# USB-I2C.net
KiCad netlist of a schematic drawn in EAGLE
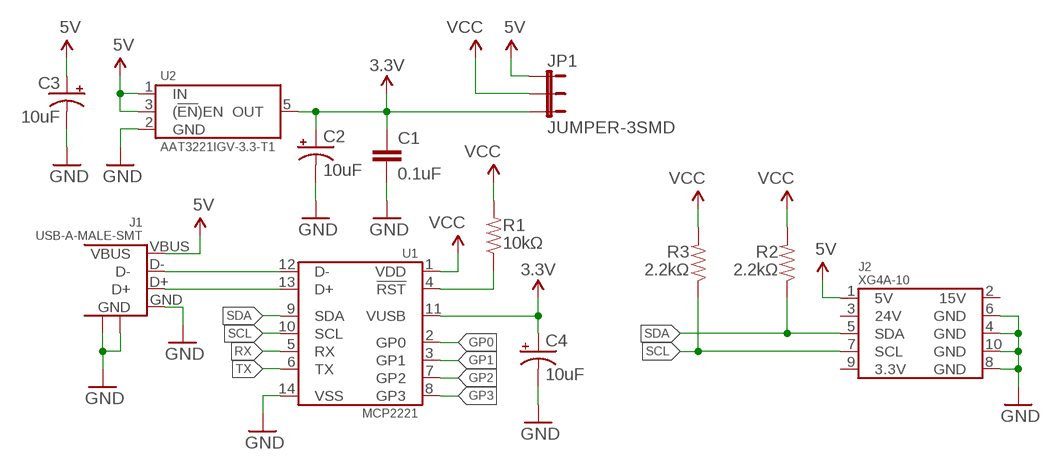
[diagram p0: schematic, sheet 1]

(export (version "E")
  (design (tool "Eeschema 10.0.6"))
  (components
    (comp (ref "C1")
      (value "0.1uF")
      (footprint "eagle-import:0805-CAP")
      (libsource (lib "eagle-import") (part "CAP-0805"))
    )
    (comp (ref "C2")
      (value "10uF")
      (footprint "eagle-import:0805-CAP_POL")
      (libsource (lib "eagle-import") (part "CAP_POL0805"))
    )
    (comp (ref "C3")
      (value "10uF")
      (footprint "eagle-import:0805-CAP_POL")
      (libsource (lib "eagle-import") (part "CAP_POL0805"))
    )
    (comp (ref "C4")
      (value "10uF")
      (footprint "eagle-import:0805-CAP_POL")
      (libsource (lib "eagle-import") (part "CAP_POL0805"))
    )
    (comp (ref "J1")
      (value "USB-A-MALE-SMT")
      (footprint "eagle-import:USB-A-MALE-SMT")
      (libsource (lib "eagle-import") (part "USB-A-MALE-SMT"))
    )
    (comp (ref "J2")
      (value "XG4A-10")
      (footprint "eagle-import:M05X2_SHROUD")
      (libsource (lib "eagle-import") (part "XG4A-10"))
    )
    (comp (ref "JP1")
      (value "JUMPER-3SMD")
      (footprint "eagle-import:SJ_3")
      (libsource (lib "eagle-import") (part "JUMPER-3SMD"))
    )
    (comp (ref "R1")
      (value "10kΩ")
      (footprint "eagle-import:0805-RES")
      (libsource (lib "eagle-import") (part "RESISTOR-0805"))
    )
    (comp (ref "R2")
      (value "2.2kΩ")
      (footprint "eagle-import:0805-RES")
      (libsource (lib "eagle-import") (part "RESISTOR-0805"))
    )
    (comp (ref "R3")
      (value "2.2kΩ")
      (footprint "eagle-import:0805-RES")
      (libsource (lib "eagle-import") (part "RESISTOR-0805"))
    )
    (comp (ref "U1")
      (value "MCP2221")
      (footprint "eagle-import:SOIC-14")
      (libsource (lib "eagle-import") (part "MCP2221"))
    )
    (comp (ref "U2")
      (value "AAT3221IGV-3.3-T1")
      (footprint "eagle-import:SOT23-5")
      (libsource (lib "eagle-import") (part "AAT3221IGV-3.3-T1"))
    )
  )
  (nets
    (net (code "1") (name "3.3V") (class "Default")
      (node (ref "C1") (pin "1") (pinfunction "1_1") (pintype "passive"))
      (node (ref "C2") (pin "A") (pinfunction "+_A") (pintype "passive"))
      (node (ref "C4") (pin "A") (pinfunction "+_A") (pintype "passive"))
      (node (ref "JP1") (pin "3") (pinfunction "3_3") (pintype "passive"))
      (node (ref "U1") (pin "11") (pinfunction "VUSB_11") (pintype "bidirectional"))
      (node (ref "U2") (pin "5") (pinfunction "OUT_5") (pintype "bidirectional"))
    )
    (net (code "2") (name "5V") (class "Default")
      (node (ref "C3") (pin "A") (pinfunction "+_A") (pintype "passive"))
      (node (ref "J1") (pin "VBUS") (pinfunction "VBUS_VBUS") (pintype "bidirectional"))
      (node (ref "J2") (pin "1") (pinfunction "5V_1") (pintype "bidirectional"))
      (node (ref "JP1") (pin "1") (pinfunction "1_1") (pintype "passive"))
      (node (ref "U2") (pin "1") (pinfunction "IN_1") (pintype "bidirectional"))
      (node (ref "U2") (pin "3") (pinfunction "(~{EN})EN_3") (pintype "bidirectional"))
    )
    (net (code "3") (name "GND") (class "Default")
      (node (ref "C1") (pin "2") (pinfunction "2_2") (pintype "passive"))
      (node (ref "C2") (pin "C") (pinfunction "-_C") (pintype "passive"))
      (node (ref "C3") (pin "C") (pinfunction "-_C") (pintype "passive"))
      (node (ref "C4") (pin "C") (pinfunction "-_C") (pintype "passive"))
      (node (ref "J1") (pin "GND") (pinfunction "GND_GND") (pintype "bidirectional"))
      (node (ref "J1") (pin "P$1") (pinfunction "P$1_P$1") (pintype "bidirectional"))
      (node (ref "J1") (pin "P$3") (pinfunction "P$2_P$3") (pintype "bidirectional"))
      (node (ref "J2") (pin "10") (pinfunction "GND_10") (pintype "bidirectional"))
      (node (ref "J2") (pin "4") (pinfunction "GND_4") (pintype "bidirectional"))
      (node (ref "J2") (pin "6") (pinfunction "GND_6") (pintype "bidirectional"))
      (node (ref "J2") (pin "8") (pinfunction "GND_8") (pintype "bidirectional"))
      (node (ref "U1") (pin "14") (pinfunction "VSS_14") (pintype "bidirectional"))
      (node (ref "U2") (pin "2") (pinfunction "GND_2") (pintype "bidirectional"))
    )
    (net (code "4") (name "GP0") (class "Default")
      (node (ref "U1") (pin "2") (pinfunction "GP0_2") (pintype "bidirectional"))
    )
    (net (code "5") (name "GP1") (class "Default")
      (node (ref "U1") (pin "3") (pinfunction "GP1_3") (pintype "bidirectional"))
    )
    (net (code "6") (name "GP2") (class "Default")
      (node (ref "U1") (pin "7") (pinfunction "GP2_7") (pintype "bidirectional"))
    )
    (net (code "7") (name "GP3") (class "Default")
      (node (ref "U1") (pin "8") (pinfunction "GP3_8") (pintype "bidirectional"))
    )
    (net (code "8") (name "Net-(U1-D+)") (class "Default")
      (node (ref "J1") (pin "D+") (pinfunction "D+_D+") (pintype "bidirectional"))
      (node (ref "U1") (pin "13") (pinfunction "D+_13") (pintype "bidirectional"))
    )
    (net (code "9") (name "Net-(U1-D-)") (class "Default")
      (node (ref "J1") (pin "D-") (pinfunction "D-_D-") (pintype "bidirectional"))
      (node (ref "U1") (pin "12") (pinfunction "D-_12") (pintype "bidirectional"))
    )
    (net (code "10") (name "Net-(U1-~{RST})") (class "Default")
      (node (ref "R1") (pin "1") (pinfunction "1_1") (pintype "passive"))
      (node (ref "U1") (pin "4") (pinfunction "~{RST}_4") (pintype "bidirectional"))
    )
    (net (code "11") (name "RX") (class "Default")
      (node (ref "U1") (pin "5") (pinfunction "RX_5") (pintype "bidirectional"))
    )
    (net (code "12") (name "SCL") (class "Default")
      (node (ref "J2") (pin "7") (pinfunction "SCL_7") (pintype "bidirectional"))
      (node (ref "R3") (pin "1") (pinfunction "1_1") (pintype "passive"))
      (node (ref "U1") (pin "10") (pinfunction "SCL_10") (pintype "bidirectional"))
    )
    (net (code "13") (name "SDA") (class "Default")
      (node (ref "J2") (pin "5") (pinfunction "SDA_5") (pintype "bidirectional"))
      (node (ref "R2") (pin "1") (pinfunction "1_1") (pintype "passive"))
      (node (ref "U1") (pin "9") (pinfunction "SDA_9") (pintype "bidirectional"))
    )
    (net (code "14") (name "TX") (class "Default")
      (node (ref "U1") (pin "6") (pinfunction "TX_6") (pintype "bidirectional"))
    )
    (net (code "15") (name "VCC") (class "Default")
      (node (ref "JP1") (pin "2") (pinfunction "2_2") (pintype "passive"))
      (node (ref "R1") (pin "2") (pinfunction "2_2") (pintype "passive"))
      (node (ref "R2") (pin "2") (pinfunction "2_2") (pintype "passive"))
      (node (ref "R3") (pin "2") (pinfunction "2_2") (pintype "passive"))
      (node (ref "U1") (pin "1") (pinfunction "VDD_1") (pintype "bidirectional"))
    )
    (net (code "16") (name "unconnected-(J2-3.3V-Pad9)") (class "Default")
      (node (ref "J2") (pin "9") (pinfunction "3.3V_9") (pintype "bidirectional"))
    )
    (net (code "17") (name "unconnected-(J2-15V-Pad2)") (class "Default")
      (node (ref "J2") (pin "2") (pinfunction "15V_2") (pintype "bidirectional"))
    )
    (net (code "18") (name "unconnected-(J2-24V-Pad3)") (class "Default")
      (node (ref "J2") (pin "3") (pinfunction "24V_3") (pintype "bidirectional"))
    )
  )
)
